# main.net
KiCad netlist of a schematic drawn in EAGLE
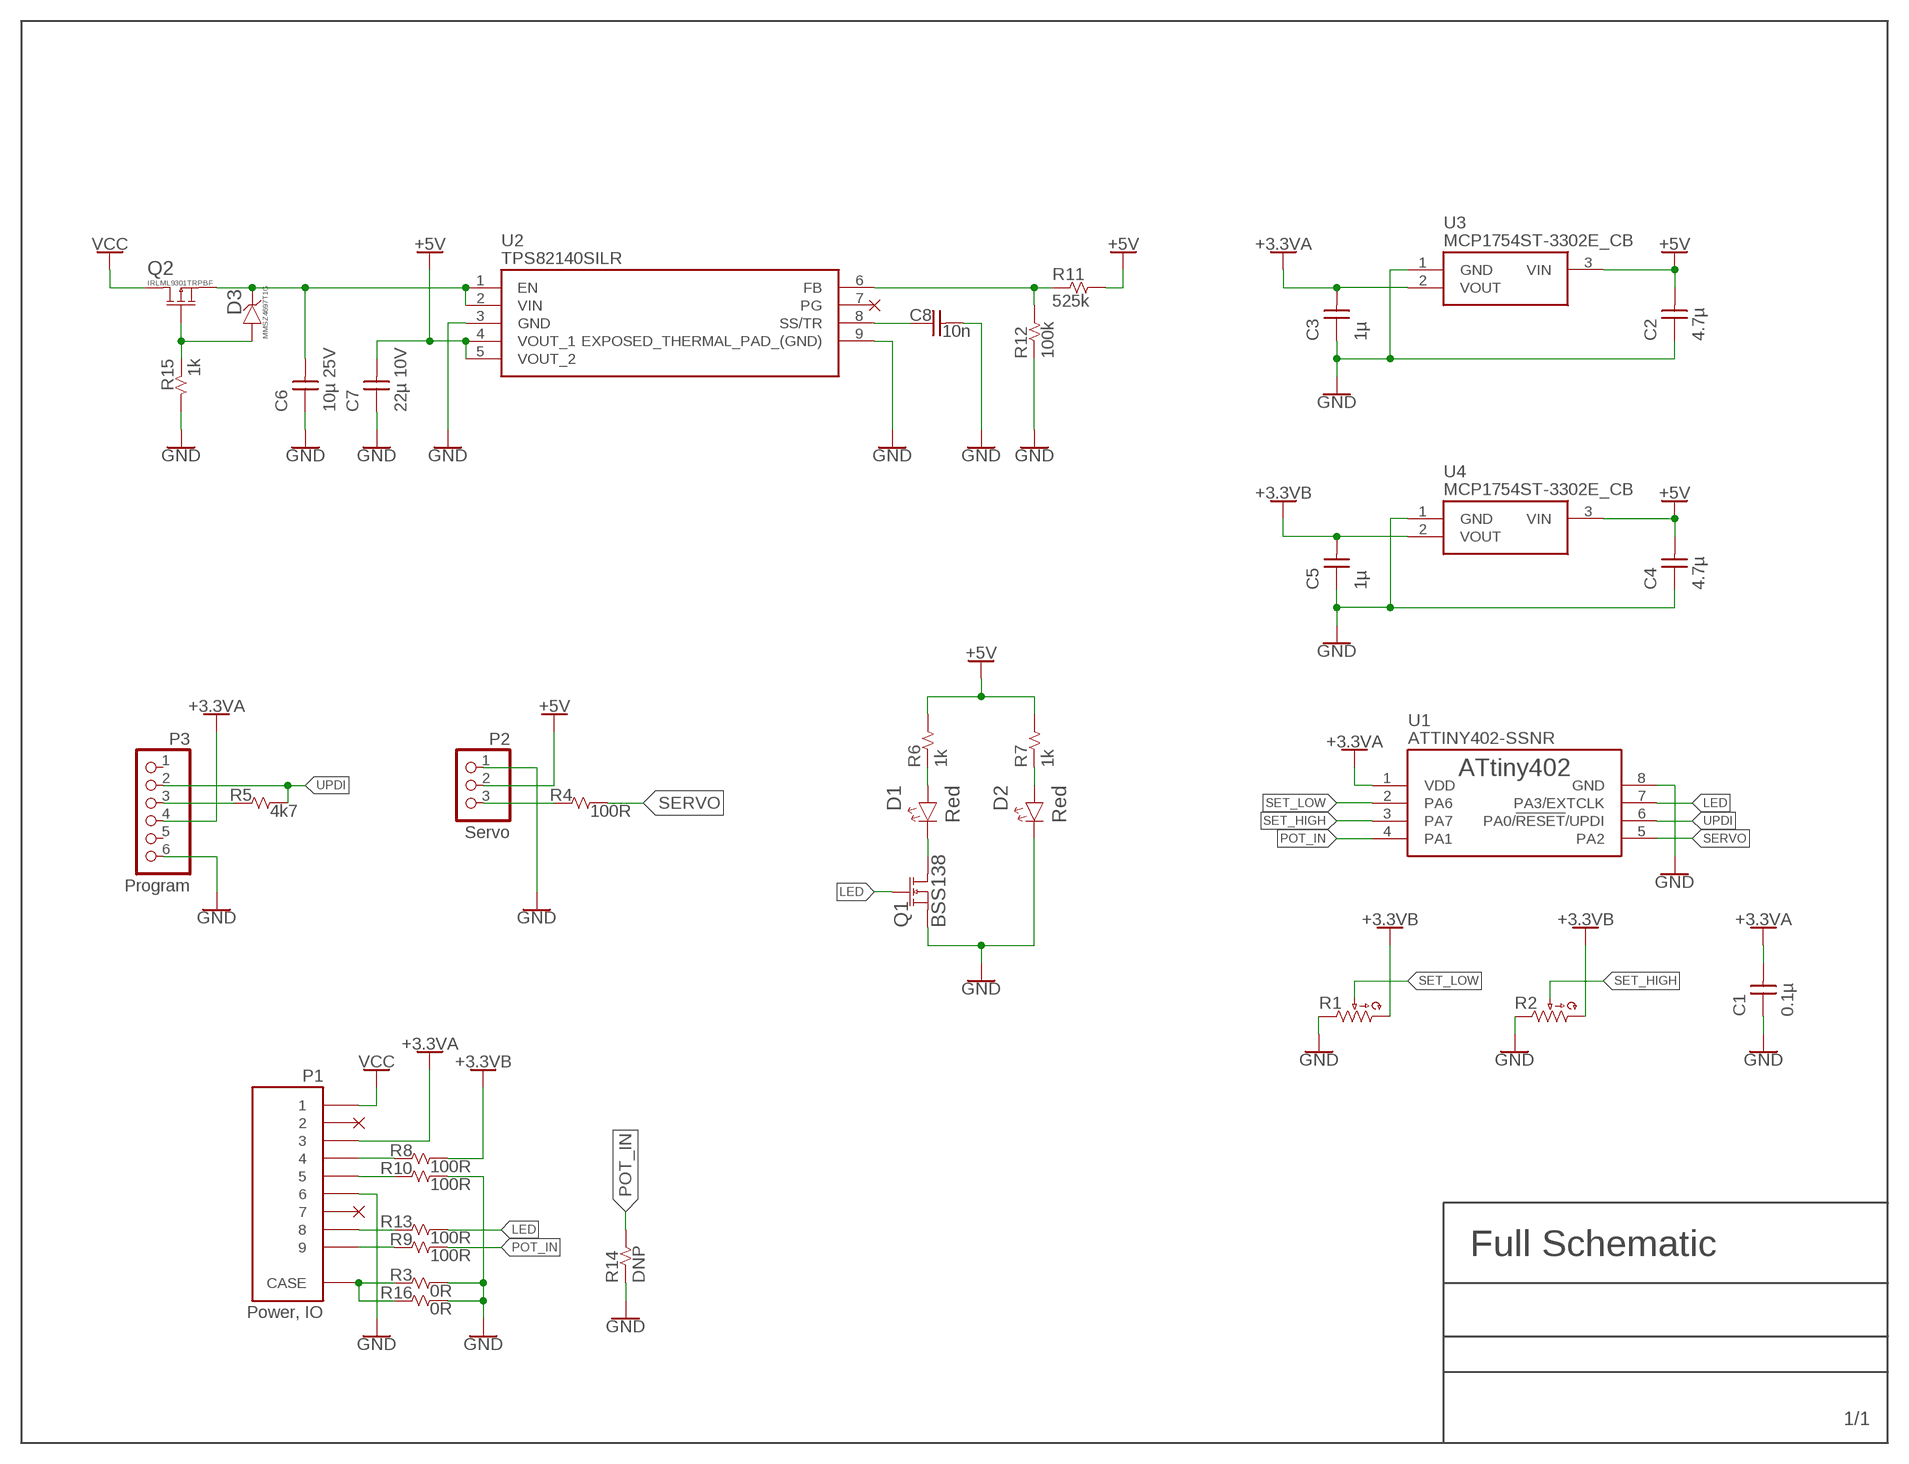
[diagram p0: schematic, sheet 1]

(export (version "E")
  (design (tool "Eeschema 10.0.6"))
  (components
    (comp (ref "C1")
      (value "0.1µ")
      (footprint "eagle-import:CAPC1608X90")
      (libsource (lib "eagle-import") (part "CAPACITOR-0603"))
    )
    (comp (ref "C2")
      (value "4.7µ")
      (footprint "eagle-import:CAPC2012X90")
      (libsource (lib "eagle-import") (part "CAPACITOR-0805"))
    )
    (comp (ref "C3")
      (value "1µ")
      (footprint "eagle-import:CAPC2012X90")
      (libsource (lib "eagle-import") (part "CAPACITOR-0805"))
    )
    (comp (ref "C4")
      (value "4.7µ")
      (footprint "eagle-import:CAPC2012X90")
      (libsource (lib "eagle-import") (part "CAPACITOR-0805"))
    )
    (comp (ref "C5")
      (value "1µ")
      (footprint "eagle-import:CAPC2012X90")
      (libsource (lib "eagle-import") (part "CAPACITOR-0805"))
    )
    (comp (ref "C6")
      (value "10µ 25V")
      (footprint "eagle-import:CAPC3216X180")
      (libsource (lib "eagle-import") (part "CAPACITOR-1206"))
    )
    (comp (ref "C7")
      (value "22µ 10V")
      (footprint "eagle-import:CAPC2012X90")
      (libsource (lib "eagle-import") (part "CAPACITOR-0805"))
    )
    (comp (ref "C8")
      (value "10n")
      (footprint "eagle-import:CAPC1608X90")
      (libsource (lib "eagle-import") (part "CAPACITOR-0603"))
    )
    (comp (ref "D1")
      (value "Red")
      (footprint "eagle-import:SODFL3216X68")
      (libsource (lib "eagle-import") (part "LED-DIALIGHT-1206"))
    )
    (comp (ref "D2")
      (value "Red")
      (footprint "eagle-import:SODFL3216X68")
      (libsource (lib "eagle-import") (part "LED-DIALIGHT-1206"))
    )
    (comp (ref "D3")
      (value "MMSZ4697T1G")
      (footprint "eagle-import:SODFL3518X115")
      (libsource (lib "eagle-import") (part "DIODE-ZENER-SOD-123F"))
    )
    (comp (ref "P1")
      (value "Power, IO")
      (footprint "eagle-import:D09P24A4GV00LF")
      (libsource (lib "eagle-import") (part "DB9"))
    )
    (comp (ref "P2")
      (value "Servo")
      (footprint "eagle-import:1X03_90")
      (libsource (lib "eagle-import") (part "PINHD-1X3/90"))
    )
    (comp (ref "P3")
      (value "Program")
      (footprint "eagle-import:1X06")
      (libsource (lib "eagle-import") (part "PINHD-1X6"))
    )
    (comp (ref "Q1")
      (value "BSS138")
      (footprint "eagle-import:SOT95P240X110-3")
      (libsource (lib "eagle-import") (part "BSS138"))
    )
    (comp (ref "Q2")
      (value "IRLML9301TRPBF")
      (footprint "eagle-import:SOT95P240X110-3")
      (libsource (lib "eagle-import") (part "IRLML9301TRPBF"))
    )
    (comp (ref "R1")
      (value "POTENTIOMETER")
      (footprint "eagle-import:TT_23B")
      (libsource (lib "eagle-import") (part "POTENTIOMETER"))
    )
    (comp (ref "R2")
      (value "POTENTIOMETER")
      (footprint "eagle-import:TT_23B")
      (libsource (lib "eagle-import") (part "POTENTIOMETER"))
    )
    (comp (ref "R3")
      (value "0R")
      (footprint "eagle-import:RESC1608X55")
      (libsource (lib "eagle-import") (part "RESISTOR-0603"))
    )
    (comp (ref "R4")
      (value "100R")
      (footprint "eagle-import:RESC1608X55")
      (libsource (lib "eagle-import") (part "RESISTOR-0603"))
    )
    (comp (ref "R5")
      (value "4k7")
      (footprint "eagle-import:RESC1608X55")
      (libsource (lib "eagle-import") (part "RESISTOR-0603"))
    )
    (comp (ref "R6")
      (value "1k")
      (footprint "eagle-import:RESC1608X55")
      (libsource (lib "eagle-import") (part "RESISTOR-0603"))
    )
    (comp (ref "R7")
      (value "1k")
      (footprint "eagle-import:RESC1608X55")
      (libsource (lib "eagle-import") (part "RESISTOR-0603"))
    )
    (comp (ref "R8")
      (value "100R")
      (footprint "eagle-import:RESC1608X55")
      (libsource (lib "eagle-import") (part "RESISTOR-0603"))
    )
    (comp (ref "R9")
      (value "100R")
      (footprint "eagle-import:RESC1608X55")
      (libsource (lib "eagle-import") (part "RESISTOR-0603"))
    )
    (comp (ref "R10")
      (value "100R")
      (footprint "eagle-import:RESC1608X55")
      (libsource (lib "eagle-import") (part "RESISTOR-0603"))
    )
    (comp (ref "R11")
      (value "525k")
      (footprint "eagle-import:RESC1608X55")
      (libsource (lib "eagle-import") (part "RESISTOR-0603"))
    )
    (comp (ref "R12")
      (value "100k")
      (footprint "eagle-import:RESC1608X55")
      (libsource (lib "eagle-import") (part "RESISTOR-0603"))
    )
    (comp (ref "R13")
      (value "100R")
      (footprint "eagle-import:RESC1608X55")
      (libsource (lib "eagle-import") (part "RESISTOR-0603"))
    )
    (comp (ref "R14")
      (value "DNP")
      (footprint "eagle-import:RESC1608X55")
      (libsource (lib "eagle-import") (part "RESISTOR-0603"))
    )
    (comp (ref "R15")
      (value "1k")
      (footprint "eagle-import:RESC1608X55")
      (libsource (lib "eagle-import") (part "RESISTOR-0603"))
    )
    (comp (ref "R16")
      (value "0R")
      (footprint "eagle-import:RESC1608X55")
      (libsource (lib "eagle-import") (part "RESISTOR-0603"))
    )
    (comp (ref "U1")
      (value "ATTINY402-SSNR")
      (footprint "eagle-import:SOIC127P599X175-8")
      (libsource (lib "eagle-import") (part "ATTINY402-SSNR"))
    )
    (comp (ref "U2")
      (value "TPS82140SILR")
      (footprint "eagle-import:SIL0008D")
      (fields (field (name "MOUSER_PART_NUMBER") "595-TPS82140SILR"))
      (libsource (lib "eagle-import") (part "TPS82140SILR"))
    )
    (comp (ref "U3")
      (value "MCP1754ST-3302E_CB")
      (footprint "eagle-import:SOT95P255X145-3N")
      (fields
        (field (name "MANUFACTURER_PART_NUMBER") "MCP1754ST-3302E/CB")
        (field (name "MOUSER_PART_NUMBER") "579-MCP1754T-3302ECB")
        (field (name "RS_PART_NUMBER") "7559521P")
      )
      (libsource (lib "eagle-import") (part "MCP1754ST-3302E_CB"))
    )
    (comp (ref "U4")
      (value "MCP1754ST-3302E_CB")
      (footprint "eagle-import:SOT95P255X145-3N")
      (fields
        (field (name "MANUFACTURER_PART_NUMBER") "MCP1754ST-3302E/CB")
        (field (name "MOUSER_PART_NUMBER") "579-MCP1754T-3302ECB")
        (field (name "RS_PART_NUMBER") "7559521P")
      )
      (libsource (lib "eagle-import") (part "MCP1754ST-3302E_CB"))
    )
  )
  (nets
    (net (code "1") (name "+3V3A") (class "Default")
      (node (ref "C1") (pin "2") (pinfunction "P$2_2") (pintype "bidirectional"))
      (node (ref "C3") (pin "2") (pinfunction "P$2_2") (pintype "bidirectional"))
      (node (ref "P1") (pin "P$3") (pinfunction "3_P$3") (pintype "passive"))
      (node (ref "P3") (pin "4") (pinfunction "4_4") (pintype "passive"))
      (node (ref "U1") (pin "1") (pinfunction "VDD_1") (pintype "power_in"))
      (node (ref "U3") (pin "2") (pinfunction "VOUT_2") (pintype "output"))
    )
    (net (code "2") (name "+3V3B") (class "Default")
      (node (ref "C5") (pin "2") (pinfunction "P$2_2") (pintype "bidirectional"))
      (node (ref "R1") (pin "P$3") (pinfunction "P$3_P$3") (pintype "passive"))
      (node (ref "R2") (pin "P$3") (pinfunction "P$3_P$3") (pintype "passive"))
      (node (ref "R8") (pin "2") (pinfunction "P$2_2") (pintype "bidirectional"))
      (node (ref "U4") (pin "2") (pinfunction "VOUT_2") (pintype "output"))
    )
    (net (code "3") (name "+5V") (class "Default")
      (node (ref "C2") (pin "2") (pinfunction "P$2_2") (pintype "bidirectional"))
      (node (ref "C4") (pin "2") (pinfunction "P$2_2") (pintype "bidirectional"))
      (node (ref "C7") (pin "2") (pinfunction "P$2_2") (pintype "bidirectional"))
      (node (ref "P2") (pin "2") (pinfunction "2_2") (pintype "passive"))
      (node (ref "R11") (pin "2") (pinfunction "P$2_2") (pintype "bidirectional"))
      (node (ref "R6") (pin "2") (pinfunction "P$2_2") (pintype "bidirectional"))
      (node (ref "R7") (pin "2") (pinfunction "P$2_2") (pintype "bidirectional"))
      (node (ref "U2") (pin "4") (pinfunction "VOUT_1_4") (pintype "bidirectional"))
      (node (ref "U2") (pin "5") (pinfunction "VOUT_2_5") (pintype "bidirectional"))
      (node (ref "U3") (pin "3") (pinfunction "VIN_3") (pintype "input"))
      (node (ref "U4") (pin "3") (pinfunction "VIN_3") (pintype "input"))
    )
    (net (code "4") (name "GND") (class "Default")
      (node (ref "C1") (pin "1") (pinfunction "P$1_1") (pintype "bidirectional"))
      (node (ref "C2") (pin "1") (pinfunction "P$1_1") (pintype "bidirectional"))
      (node (ref "C3") (pin "1") (pinfunction "P$1_1") (pintype "bidirectional"))
      (node (ref "C4") (pin "1") (pinfunction "P$1_1") (pintype "bidirectional"))
      (node (ref "C5") (pin "1") (pinfunction "P$1_1") (pintype "bidirectional"))
      (node (ref "C6") (pin "1") (pinfunction "P$1_1") (pintype "bidirectional"))
      (node (ref "C7") (pin "1") (pinfunction "P$1_1") (pintype "bidirectional"))
      (node (ref "C8") (pin "2") (pinfunction "P$2_2") (pintype "bidirectional"))
      (node (ref "D2") (pin "1") (pinfunction "C_1") (pintype "passive"))
      (node (ref "P1") (pin "P$6") (pinfunction "6_P$6") (pintype "passive"))
      (node (ref "P2") (pin "1") (pinfunction "1_1") (pintype "passive"))
      (node (ref "P3") (pin "6") (pinfunction "6_6") (pintype "passive"))
      (node (ref "Q1") (pin "2") (pinfunction "S_2") (pintype "bidirectional"))
      (node (ref "R1") (pin "P$1") (pinfunction "P$1_P$1") (pintype "passive"))
      (node (ref "R10") (pin "2") (pinfunction "P$2_2") (pintype "bidirectional"))
      (node (ref "R12") (pin "1") (pinfunction "P$1_1") (pintype "bidirectional"))
      (node (ref "R14") (pin "1") (pinfunction "P$1_1") (pintype "bidirectional"))
      (node (ref "R15") (pin "2") (pinfunction "P$2_2") (pintype "bidirectional"))
      (node (ref "R16") (pin "2") (pinfunction "P$2_2") (pintype "bidirectional"))
      (node (ref "R2") (pin "P$1") (pinfunction "P$1_P$1") (pintype "passive"))
      (node (ref "R3") (pin "2") (pinfunction "P$2_2") (pintype "bidirectional"))
      (node (ref "U1") (pin "8") (pinfunction "GND_8") (pintype "power_in"))
      (node (ref "U2") (pin "3") (pinfunction "GND_3") (pintype "bidirectional"))
      (node (ref "U2") (pin "9") (pinfunction "EXPOSED_THERMAL_PAD_(GND)_9") (pintype "bidirectional"))
      (node (ref "U3") (pin "1") (pinfunction "GND_1") (pintype "power_in"))
      (node (ref "U4") (pin "1") (pinfunction "GND_1") (pintype "power_in"))
    )
    (net (code "5") (name "LED") (class "Default")
      (node (ref "Q1") (pin "1") (pinfunction "G_1") (pintype "bidirectional"))
      (node (ref "R13") (pin "2") (pinfunction "P$2_2") (pintype "bidirectional"))
      (node (ref "U1") (pin "7") (pinfunction "PA3/EXTCLK_7") (pintype "bidirectional"))
    )
    (net (code "6") (name "Net-(C6-P$2)") (class "Default")
      (node (ref "C6") (pin "2") (pinfunction "P$2_2") (pintype "bidirectional"))
      (node (ref "D3") (pin "1") (pinfunction "C_1") (pintype "passive"))
      (node (ref "Q2") (pin "2") (pinfunction "S_2") (pintype "bidirectional"))
      (node (ref "U2") (pin "1") (pinfunction "EN_1") (pintype "bidirectional"))
      (node (ref "U2") (pin "2") (pinfunction "VIN_2") (pintype "bidirectional"))
    )
    (net (code "7") (name "Net-(C8-P$1)") (class "Default")
      (node (ref "C8") (pin "1") (pinfunction "P$1_1") (pintype "bidirectional"))
      (node (ref "U2") (pin "8") (pinfunction "SS/TR_8") (pintype "bidirectional"))
    )
    (net (code "8") (name "Net-(D1-A)") (class "Default")
      (node (ref "D1") (pin "2") (pinfunction "A_2") (pintype "passive"))
      (node (ref "R6") (pin "1") (pinfunction "P$1_1") (pintype "bidirectional"))
    )
    (net (code "9") (name "Net-(D1-C)") (class "Default")
      (node (ref "D1") (pin "1") (pinfunction "C_1") (pintype "passive"))
      (node (ref "Q1") (pin "3") (pinfunction "D_3") (pintype "bidirectional"))
    )
    (net (code "10") (name "Net-(D2-A)") (class "Default")
      (node (ref "D2") (pin "2") (pinfunction "A_2") (pintype "passive"))
      (node (ref "R7") (pin "1") (pinfunction "P$1_1") (pintype "bidirectional"))
    )
    (net (code "11") (name "Net-(D3-A)") (class "Default")
      (node (ref "D3") (pin "2") (pinfunction "A_2") (pintype "passive"))
      (node (ref "Q2") (pin "1") (pinfunction "G_1") (pintype "bidirectional"))
      (node (ref "R15") (pin "1") (pinfunction "P$1_1") (pintype "bidirectional"))
    )
    (net (code "12") (name "Net-(P1-4)") (class "Default")
      (node (ref "P1") (pin "P$4") (pinfunction "4_P$4") (pintype "passive"))
      (node (ref "R8") (pin "1") (pinfunction "P$1_1") (pintype "bidirectional"))
    )
    (net (code "13") (name "Net-(P1-5)") (class "Default")
      (node (ref "P1") (pin "P$5") (pinfunction "5_P$5") (pintype "passive"))
      (node (ref "R10") (pin "1") (pinfunction "P$1_1") (pintype "bidirectional"))
    )
    (net (code "14") (name "Net-(P1-8)") (class "Default")
      (node (ref "P1") (pin "P$8") (pinfunction "8_P$8") (pintype "passive"))
      (node (ref "R13") (pin "1") (pinfunction "P$1_1") (pintype "bidirectional"))
    )
    (net (code "15") (name "Net-(P1-9)") (class "Default")
      (node (ref "P1") (pin "P$9") (pinfunction "9_P$9") (pintype "passive"))
      (node (ref "R9") (pin "1") (pinfunction "P$1_1") (pintype "bidirectional"))
    )
    (net (code "16") (name "Net-(R4-P$1)") (class "Default")
      (node (ref "P2") (pin "3") (pinfunction "3_3") (pintype "passive"))
      (node (ref "R4") (pin "1") (pinfunction "P$1_1") (pintype "bidirectional"))
    )
    (net (code "17") (name "Net-(R5-P$1)") (class "Default")
      (node (ref "P3") (pin "3") (pinfunction "3_3") (pintype "passive"))
      (node (ref "R5") (pin "1") (pinfunction "P$1_1") (pintype "bidirectional"))
    )
    (net (code "18") (name "Net-(R11-P$1)") (class "Default")
      (node (ref "R11") (pin "1") (pinfunction "P$1_1") (pintype "bidirectional"))
      (node (ref "R12") (pin "2") (pinfunction "P$2_2") (pintype "bidirectional"))
      (node (ref "U2") (pin "6") (pinfunction "FB_6") (pintype "bidirectional"))
    )
    (net (code "19") (name "Net-(R16-P$1)") (class "Default")
      (node (ref "P1") (pin "P$10") (pinfunction "CASE_P$10") (pintype "passive"))
      (node (ref "P1") (pin "P$11") (pinfunction "CASE_P$11") (pintype "passive"))
      (node (ref "R16") (pin "1") (pinfunction "P$1_1") (pintype "bidirectional"))
      (node (ref "R3") (pin "1") (pinfunction "P$1_1") (pintype "bidirectional"))
    )
    (net (code "20") (name "POT_IN") (class "Default")
      (node (ref "R14") (pin "2") (pinfunction "P$2_2") (pintype "bidirectional"))
      (node (ref "R9") (pin "2") (pinfunction "P$2_2") (pintype "bidirectional"))
      (node (ref "U1") (pin "4") (pinfunction "PA1_4") (pintype "bidirectional"))
    )
    (net (code "21") (name "SERVO") (class "Default")
      (node (ref "R4") (pin "2") (pinfunction "P$2_2") (pintype "bidirectional"))
      (node (ref "U1") (pin "5") (pinfunction "PA2_5") (pintype "bidirectional"))
    )
    (net (code "22") (name "SET_HIGH") (class "Default")
      (node (ref "R2") (pin "P$2") (pinfunction "P$2_P$2") (pintype "passive"))
      (node (ref "U1") (pin "3") (pinfunction "PA7_3") (pintype "bidirectional"))
    )
    (net (code "23") (name "SET_LOW") (class "Default")
      (node (ref "R1") (pin "P$2") (pinfunction "P$2_P$2") (pintype "passive"))
      (node (ref "U1") (pin "2") (pinfunction "PA6_2") (pintype "bidirectional"))
    )
    (net (code "24") (name "UPDI") (class "Default")
      (node (ref "P3") (pin "2") (pinfunction "2_2") (pintype "passive"))
      (node (ref "R5") (pin "2") (pinfunction "P$2_2") (pintype "bidirectional"))
      (node (ref "U1") (pin "6") (pinfunction "PA0/~{RESET}/UPDI_6") (pintype "bidirectional"))
    )
    (net (code "25") (name "VCC") (class "Default")
      (node (ref "P1") (pin "P$1") (pinfunction "1_P$1") (pintype "passive"))
      (node (ref "Q2") (pin "3") (pinfunction "D_3") (pintype "bidirectional"))
    )
    (net (code "26") (name "unconnected-(P1-2-PadP$2)") (class "Default")
      (node (ref "P1") (pin "P$2") (pinfunction "2_P$2") (pintype "passive"))
    )
    (net (code "27") (name "unconnected-(P1-7-PadP$7)") (class "Default")
      (node (ref "P1") (pin "P$7") (pinfunction "7_P$7") (pintype "passive"))
    )
    (net (code "28") (name "unconnected-(P3-Pad1)") (class "Default")
      (node (ref "P3") (pin "1") (pinfunction "1_1") (pintype "passive"))
    )
    (net (code "29") (name "unconnected-(P3-Pad5)") (class "Default")
      (node (ref "P3") (pin "5") (pinfunction "5_5") (pintype "passive"))
    )
    (net (code "30") (name "unconnected-(U2-PG-Pad7)") (class "Default")
      (node (ref "U2") (pin "7") (pinfunction "PG_7") (pintype "bidirectional"))
    )
  )
)
